# Filters.net
KiCad netlist of a schematic drawn in Altium Designer
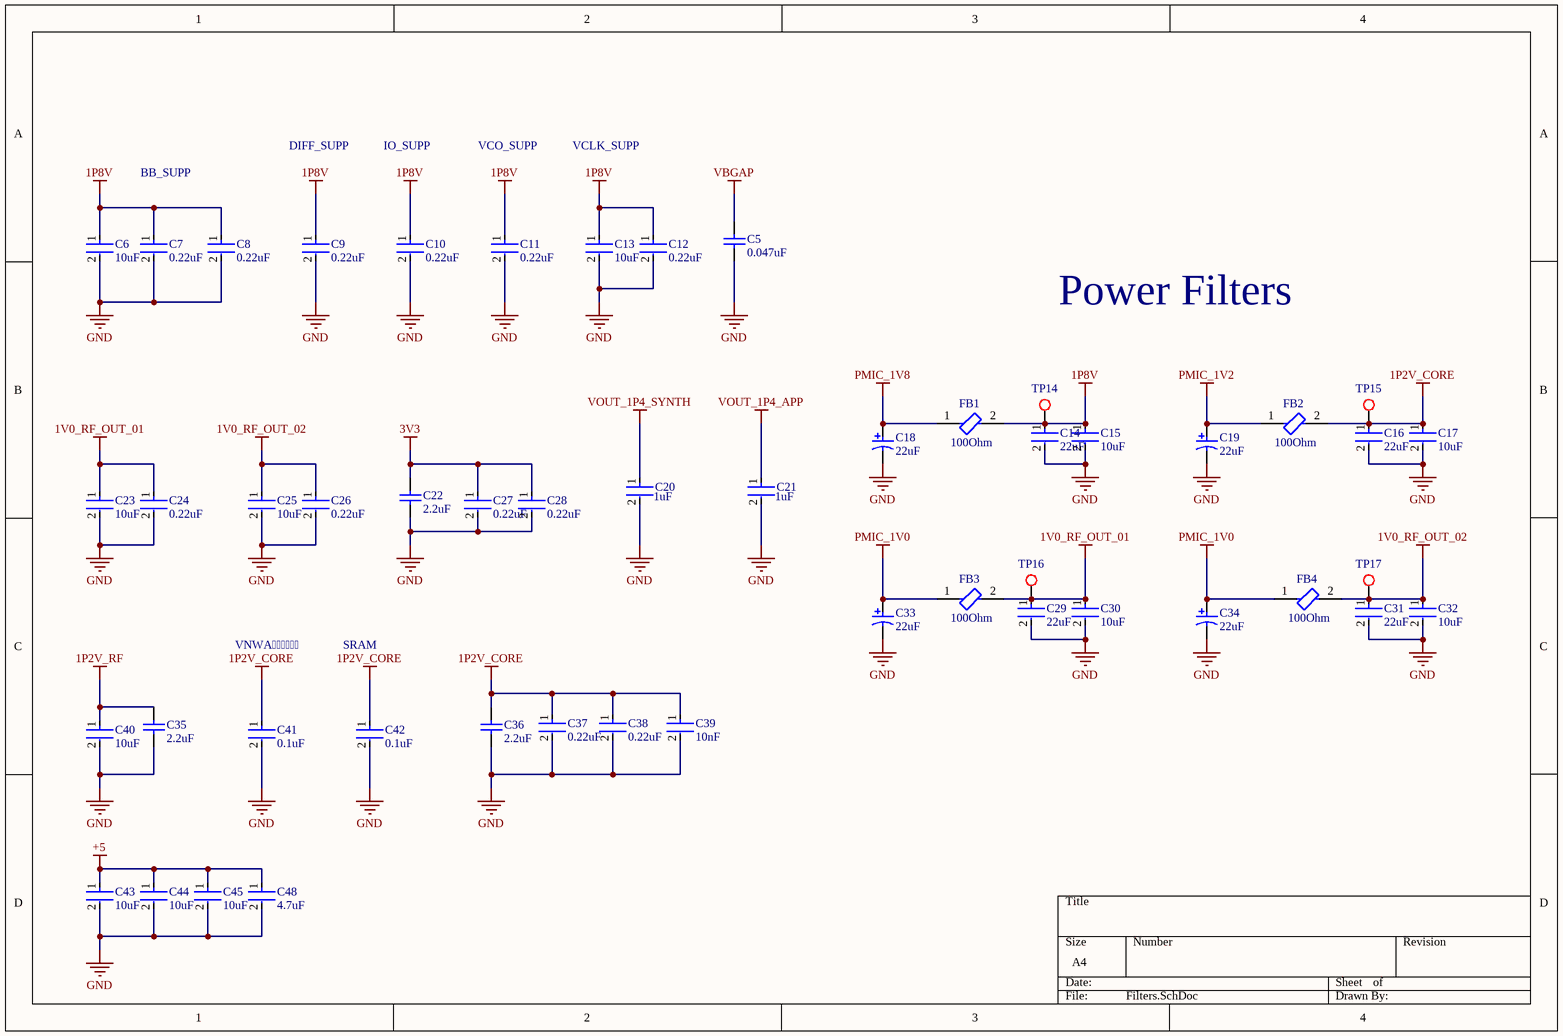
[diagram p0: Filters.SchDoc]

(export (version "E")
  (design (tool "Eeschema 10.0.6"))
  (components
    (comp (ref "C5")
      (value "0.047uF")
      (footprint "CAPC1608X90X35NL15T15")
      (fields
        (field (name "MANUFACTURER") "AVX Interconnect / Elco")
        (field (name "PART NUMBER") "06035F473K4T2A")
      )
      (libsource (lib "Altium Content Vault") (part "CAP"))
    )
    (comp (ref "C6")
      (value "10uF")
      (footprint "FP-GRM18-0_15-MFG")
      (description "CAP CER 10UF 10V X5R 0603")
      (fields
        (field (name "OCTOPART") "https://octopart.com/grm188r61a106ke69d-murata-22851381")
        (field (name "MANUFACTURER PART NUMBER") "GRM188R61A106KE69D")
      )
      (libsource (lib "Altium Content Vault") (part "11868f565c42a9108669ba33697ecf6"))
    )
    (comp (ref "C7")
      (value "0.22uF")
      (footprint "FP-C0603C-CF-MFG")
      (description "C0603 0.22 μF X7R 30ppm/°C 10.00% 10 V")
      (fields (field (name "TOLERANCE") "0.1") (field (name "MANUFACTURER PART NUMBER") "C0603C224K8RAC"))
      (libsource (lib "Altium Content Vault") (part "b4654b650e69147ec39a6b967a45e02"))
    )
    (comp (ref "C8")
      (value "0.22uF")
      (footprint "FP-C0603C-CF-MFG")
      (description "C0603 0.22 μF X7R 30ppm/°C 10.00% 10 V")
      (fields (field (name "TOLERANCE") "0.1") (field (name "MANUFACTURER PART NUMBER") "C0603C224K8RAC"))
      (libsource (lib "Altium Content Vault") (part "b4654b650e69147ec39a6b967a45e02"))
    )
    (comp (ref "C9")
      (value "0.22uF")
      (footprint "FP-C0603C-CF-MFG")
      (description "C0603 0.22 μF X7R 30ppm/°C 10.00% 10 V")
      (fields (field (name "TOLERANCE") "0.1") (field (name "MANUFACTURER PART NUMBER") "C0603C224K8RAC"))
      (libsource (lib "Altium Content Vault") (part "b4654b650e69147ec39a6b967a45e02"))
    )
    (comp (ref "C10")
      (value "0.22uF")
      (footprint "FP-C0603C-CF-MFG")
      (description "C0603 0.22 μF X7R 30ppm/°C 10.00% 10 V")
      (fields (field (name "TOLERANCE") "0.1") (field (name "MANUFACTURER PART NUMBER") "C0603C224K8RAC"))
      (libsource (lib "Altium Content Vault") (part "b4654b650e69147ec39a6b967a45e02"))
    )
    (comp (ref "C11")
      (value "0.22uF")
      (footprint "FP-C0603C-CF-MFG")
      (description "C0603 0.22 μF X7R 30ppm/°C 10.00% 10 V")
      (fields (field (name "TOLERANCE") "0.1") (field (name "MANUFACTURER PART NUMBER") "C0603C224K8RAC"))
      (libsource (lib "Altium Content Vault") (part "b4654b650e69147ec39a6b967a45e02"))
    )
    (comp (ref "C12")
      (value "0.22uF")
      (footprint "FP-C0603C-CF-MFG")
      (description "C0603 0.22 μF X7R 30ppm/°C 10.00% 10 V")
      (fields (field (name "TOLERANCE") "0.1") (field (name "MANUFACTURER PART NUMBER") "C0603C224K8RAC"))
      (libsource (lib "Altium Content Vault") (part "b4654b650e69147ec39a6b967a45e02"))
    )
    (comp (ref "C13")
      (value "10uF")
      (footprint "FP-GRM18-0_15-MFG")
      (description "CAP CER 10UF 10V X5R 0603")
      (fields
        (field (name "OCTOPART") "https://octopart.com/grm188r61a106ke69d-murata-22851381")
        (field (name "MANUFACTURER PART NUMBER") "GRM188R61A106KE69D")
      )
      (libsource (lib "Altium Content Vault") (part "11868f565c42a9108669ba33697ecf6"))
    )
    (comp (ref "C14")
      (value "22uF")
      (footprint "FP-CL21-IPC_C")
      (description "CL21 Series 0805 22uF 4V ±20% Tolerance X6S Multilayer Ceramic Chip Capacitor")
      (fields (field (name "TOLERANCE") "20%"))
      (libsource (lib "Altium Content Vault") (part "b4654b650e69147ec39a6b967a45e02"))
    )
    (comp (ref "C15")
      (value "10uF")
      (footprint "FP-GRM18-0_15-MFG")
      (description "CAP CER 10UF 10V X5R 0603")
      (fields
        (field (name "OCTOPART") "https://octopart.com/grm188r61a106ke69d-murata-22851381")
        (field (name "MANUFACTURER PART NUMBER") "GRM188R61A106KE69D")
      )
      (libsource (lib "Altium Content Vault") (part "11868f565c42a9108669ba33697ecf6"))
    )
    (comp (ref "C16")
      (value "22uF")
      (footprint "FP-CL21-IPC_C")
      (description "CL21 Series 0805 22uF 4V ±20% Tolerance X6S Multilayer Ceramic Chip Capacitor")
      (fields (field (name "TOLERANCE") "20%"))
      (libsource (lib "Altium Content Vault") (part "b4654b650e69147ec39a6b967a45e02"))
    )
    (comp (ref "C17")
      (value "10uF")
      (footprint "FP-GRM18-0_15-MFG")
      (description "CAP CER 10UF 10V X5R 0603")
      (fields
        (field (name "OCTOPART") "https://octopart.com/grm188r61a106ke69d-murata-22851381")
        (field (name "MANUFACTURER PART NUMBER") "GRM188R61A106KE69D")
      )
      (libsource (lib "Altium Content Vault") (part "11868f565c42a9108669ba33697ecf6"))
    )
    (comp (ref "C18")
      (value "22uF")
      (footprint "NIC-CAPA2-4X5.8_V")
      (fields (field (name "MANUFACTURER") "Nichicon") (field (name "PARTNUMBER") "UUD1A220MCL1GS"))
      (libsource (lib "Altium Content Vault") (part "NIC-CAP-P-2"))
    )
    (comp (ref "C19")
      (value "22uF")
      (footprint "NIC-CAPA2-4X5.8_V")
      (fields (field (name "MANUFACTURER") "Nichicon") (field (name "PARTNUMBER") "UUD1A220MCL1GS"))
      (libsource (lib "Altium Content Vault") (part "NIC-CAP-P-2"))
    )
    (comp (ref "C20")
      (value "1uF")
      (footprint "FP-CL10-IPC_C")
      (description "Cap Ceramic 1uF 10V X5R ±10% Pad SMD 0603 +85°C T/R")
      (fields (field (name "VOLTAGE") "10V") (field (name "TOLERANCE") "10%"))
      (libsource (lib "Altium Content Vault") (part "b4654b650e69147ec39a6b967a45e02"))
    )
    (comp (ref "C21")
      (value "1uF")
      (footprint "FP-CL10-IPC_C")
      (description "Cap Ceramic 1uF 10V X5R ±10% Pad SMD 0603 +85°C T/R")
      (fields (field (name "VOLTAGE") "10V") (field (name "TOLERANCE") "10%"))
      (libsource (lib "Altium Content Vault") (part "b4654b650e69147ec39a6b967a45e02"))
    )
    (comp (ref "C22")
      (value "2.2uF")
      (footprint "CAPC0603(1608)100_N")
      (description "CAP 2.2uF 16V -20% to +80% 0603 (1608 Metric) Thickness 1mm SMD")
      (fields (field (name "TOLERANCE") "-20% to +80%"))
      (libsource (lib "Altium Content Vault") (part "CAP"))
    )
    (comp (ref "C23")
      (value "10uF")
      (footprint "FP-GRM18-0_15-MFG")
      (description "CAP CER 10UF 10V X5R 0603")
      (fields
        (field (name "OCTOPART") "https://octopart.com/grm188r61a106ke69d-murata-22851381")
        (field (name "MANUFACTURER PART NUMBER") "GRM188R61A106KE69D")
      )
      (libsource (lib "Altium Content Vault") (part "11868f565c42a9108669ba33697ecf6"))
    )
    (comp (ref "C24")
      (value "0.22uF")
      (footprint "FP-C0603C-CF-MFG")
      (description "C0603 0.22 μF X7R 30ppm/°C 10.00% 10 V")
      (fields (field (name "TOLERANCE") "0.1") (field (name "MANUFACTURER PART NUMBER") "C0603C224K8RAC"))
      (libsource (lib "Altium Content Vault") (part "b4654b650e69147ec39a6b967a45e02"))
    )
    (comp (ref "C25")
      (value "10uF")
      (footprint "FP-GRM18-0_15-MFG")
      (description "CAP CER 10UF 10V X5R 0603")
      (fields
        (field (name "OCTOPART") "https://octopart.com/grm188r61a106ke69d-murata-22851381")
        (field (name "MANUFACTURER PART NUMBER") "GRM188R61A106KE69D")
      )
      (libsource (lib "Altium Content Vault") (part "11868f565c42a9108669ba33697ecf6"))
    )
    (comp (ref "C26")
      (value "0.22uF")
      (footprint "FP-C0603C-CF-MFG")
      (description "C0603 0.22 μF X7R 30ppm/°C 10.00% 10 V")
      (fields (field (name "TOLERANCE") "0.1") (field (name "MANUFACTURER PART NUMBER") "C0603C224K8RAC"))
      (libsource (lib "Altium Content Vault") (part "b4654b650e69147ec39a6b967a45e02"))
    )
    (comp (ref "C27")
      (value "0.22uF")
      (footprint "FP-C0603C-CF-MFG")
      (description "C0603 0.22 μF X7R 30ppm/°C 10.00% 10 V")
      (fields (field (name "TOLERANCE") "0.1") (field (name "MANUFACTURER PART NUMBER") "C0603C224K8RAC"))
      (libsource (lib "Altium Content Vault") (part "b4654b650e69147ec39a6b967a45e02"))
    )
    (comp (ref "C28")
      (value "0.22uF")
      (footprint "FP-C0603C-CF-MFG")
      (description "C0603 0.22 μF X7R 30ppm/°C 10.00% 10 V")
      (fields (field (name "TOLERANCE") "0.1") (field (name "MANUFACTURER PART NUMBER") "C0603C224K8RAC"))
      (libsource (lib "Altium Content Vault") (part "b4654b650e69147ec39a6b967a45e02"))
    )
    (comp (ref "C29")
      (value "22uF")
      (footprint "FP-CL21-IPC_C")
      (description "CL21 Series 0805 22uF 4V ±20% Tolerance X6S Multilayer Ceramic Chip Capacitor")
      (fields (field (name "TOLERANCE") "20%"))
      (libsource (lib "Altium Content Vault") (part "b4654b650e69147ec39a6b967a45e02"))
    )
    (comp (ref "C30")
      (value "10uF")
      (footprint "FP-GRM18-0_15-MFG")
      (description "CAP CER 10UF 10V X5R 0603")
      (fields
        (field (name "OCTOPART") "https://octopart.com/grm188r61a106ke69d-murata-22851381")
        (field (name "MANUFACTURER PART NUMBER") "GRM188R61A106KE69D")
      )
      (libsource (lib "Altium Content Vault") (part "11868f565c42a9108669ba33697ecf6"))
    )
    (comp (ref "C31")
      (value "22uF")
      (footprint "FP-CL21-IPC_C")
      (description "CL21 Series 0805 22uF 4V ±20% Tolerance X6S Multilayer Ceramic Chip Capacitor")
      (fields (field (name "TOLERANCE") "20%"))
      (libsource (lib "Altium Content Vault") (part "b4654b650e69147ec39a6b967a45e02"))
    )
    (comp (ref "C32")
      (value "10uF")
      (footprint "FP-GRM18-0_15-MFG")
      (description "CAP CER 10UF 10V X5R 0603")
      (fields
        (field (name "OCTOPART") "https://octopart.com/grm188r61a106ke69d-murata-22851381")
        (field (name "MANUFACTURER PART NUMBER") "GRM188R61A106KE69D")
      )
      (libsource (lib "Altium Content Vault") (part "11868f565c42a9108669ba33697ecf6"))
    )
    (comp (ref "C33")
      (value "22uF")
      (footprint "NIC-CAPA2-4X5.8_V")
      (fields (field (name "MANUFACTURER") "Nichicon") (field (name "PARTNUMBER") "UUD1A220MCL1GS"))
      (libsource (lib "Altium Content Vault") (part "NIC-CAP-P-2"))
    )
    (comp (ref "C34")
      (value "22uF")
      (footprint "NIC-CAPA2-4X5.8_V")
      (fields (field (name "MANUFACTURER") "Nichicon") (field (name "PARTNUMBER") "UUD1A220MCL1GS"))
      (libsource (lib "Altium Content Vault") (part "NIC-CAP-P-2"))
    )
    (comp (ref "C35")
      (value "2.2uF")
      (footprint "CAPC0603(1608)100_N")
      (description "CAP 2.2uF 16V -20% to +80% 0603 (1608 Metric) Thickness 1mm SMD")
      (fields (field (name "TOLERANCE") "-20% to +80%"))
      (libsource (lib "Altium Content Vault") (part "CAP"))
    )
    (comp (ref "C36")
      (value "2.2uF")
      (footprint "CAPC0603(1608)100_N")
      (description "CAP 2.2uF 16V -20% to +80% 0603 (1608 Metric) Thickness 1mm SMD")
      (fields (field (name "TOLERANCE") "-20% to +80%"))
      (libsource (lib "Altium Content Vault") (part "CAP"))
    )
    (comp (ref "C37")
      (value "0.22uF")
      (footprint "FP-C0603C-CF-MFG")
      (description "C0603 0.22 μF X7R 30ppm/°C 10.00% 10 V")
      (fields (field (name "TOLERANCE") "0.1") (field (name "MANUFACTURER PART NUMBER") "C0603C224K8RAC"))
      (libsource (lib "Altium Content Vault") (part "b4654b650e69147ec39a6b967a45e02"))
    )
    (comp (ref "C38")
      (value "0.22uF")
      (footprint "FP-C0603C-CF-MFG")
      (description "C0603 0.22 μF X7R 30ppm/°C 10.00% 10 V")
      (fields (field (name "TOLERANCE") "0.1") (field (name "MANUFACTURER PART NUMBER") "C0603C224K8RAC"))
      (libsource (lib "Altium Content Vault") (part "b4654b650e69147ec39a6b967a45e02"))
    )
    (comp (ref "C39")
      (value "10nF")
      (footprint "FP-CGA3E-0_3-0_1-IPC_A")
      (description "Cap Ceramic 10nF 100V X8R 10% Pad SMD 0603 +150°C Automotive T/R")
      (fields (field (name "TOLERANCE") "10%"))
      (libsource (lib "Altium Content Vault") (part "b4654b650e69147ec39a6b967a45e02"))
    )
    (comp (ref "C40")
      (value "10uF")
      (footprint "FP-GRM18-0_15-MFG")
      (description "CAP CER 10UF 10V X5R 0603")
      (fields
        (field (name "OCTOPART") "https://octopart.com/grm188r61a106ke69d-murata-22851381")
        (field (name "MANUFACTURER PART NUMBER") "GRM188R61A106KE69D")
      )
      (libsource (lib "Altium Content Vault") (part "11868f565c42a9108669ba33697ecf6"))
    )
    (comp (ref "C41")
      (value "0.1uF")
      (footprint "FP-CC0603-DA-MFG")
      (description "CAP CER 0.1UF 10V X7R 0603")
      (fields
        (field (name "OCTOPART") "https://octopart.com/cc0603krx7r6bb104-yageo-9291607")
        (field (name "TOLERANCE") "0.1")
      )
      (libsource (lib "Altium Content Vault") (part "11868f565c42a9108669ba33697ecf6"))
    )
    (comp (ref "C42")
      (value "0.1uF")
      (footprint "FP-CC0603-DA-MFG")
      (description "CAP CER 0.1UF 10V X7R 0603")
      (fields
        (field (name "OCTOPART") "https://octopart.com/cc0603krx7r6bb104-yageo-9291607")
        (field (name "TOLERANCE") "0.1")
      )
      (libsource (lib "Altium Content Vault") (part "11868f565c42a9108669ba33697ecf6"))
    )
    (comp (ref "C43")
      (value "10uF")
      (footprint "FP-GRM18-0_15-MFG")
      (description "CAP CER 10UF 10V X5R 0603")
      (fields
        (field (name "OCTOPART") "https://octopart.com/grm188r61a106ke69d-murata-22851381")
        (field (name "MANUFACTURER PART NUMBER") "GRM188R61A106KE69D")
      )
      (libsource (lib "Altium Content Vault") (part "11868f565c42a9108669ba33697ecf6"))
    )
    (comp (ref "C44")
      (value "10uF")
      (footprint "FP-GRM18-0_15-MFG")
      (description "CAP CER 10UF 10V X5R 0603")
      (fields
        (field (name "OCTOPART") "https://octopart.com/grm188r61a106ke69d-murata-22851381")
        (field (name "MANUFACTURER PART NUMBER") "GRM188R61A106KE69D")
      )
      (libsource (lib "Altium Content Vault") (part "11868f565c42a9108669ba33697ecf6"))
    )
    (comp (ref "C45")
      (value "10uF")
      (footprint "FP-GRM18-0_15-MFG")
      (description "CAP CER 10UF 10V X5R 0603")
      (fields
        (field (name "OCTOPART") "https://octopart.com/grm188r61a106ke69d-murata-22851381")
        (field (name "MANUFACTURER PART NUMBER") "GRM188R61A106KE69D")
      )
      (libsource (lib "Altium Content Vault") (part "11868f565c42a9108669ba33697ecf6"))
    )
    (comp (ref "C48")
      (value "4.7uF")
      (footprint "FP-CL10-IPC_A")
      (description "Cap Ceramic 4.7uF 6.3V X6S ±10% Pad SMD 0603 +105°C T/R")
      (fields (field (name "TOLERANCE") "10%"))
      (libsource (lib "Altium Content Vault") (part "b4654b650e69147ec39a6b967a45e02"))
    )
    (comp (ref "FB1")
      (value "100Ohm")
      (footprint "FP-MPZ1608-0_8-MFG")
      (description "Power line Ferrite Bead 100Ω @ 100MHz 2A DCR 0.04Ω AEC-Q200 SMD 0603")
      (fields (field (name "TOLERANCE") "25%"))
      (libsource (lib "Altium Content Vault") (part "5f30dd21d616792df468990f7003faa"))
    )
    (comp (ref "FB2")
      (value "100Ohm")
      (footprint "FP-MPZ1608-0_8-MFG")
      (description "Power line Ferrite Bead 100Ω @ 100MHz 2A DCR 0.04Ω AEC-Q200 SMD 0603")
      (fields (field (name "TOLERANCE") "25%"))
      (libsource (lib "Altium Content Vault") (part "5f30dd21d616792df468990f7003faa"))
    )
    (comp (ref "FB3")
      (value "100Ohm")
      (footprint "FP-MPZ1608-0_8-MFG")
      (description "Power line Ferrite Bead 100Ω @ 100MHz 2A DCR 0.04Ω AEC-Q200 SMD 0603")
      (fields (field (name "TOLERANCE") "25%"))
      (libsource (lib "Altium Content Vault") (part "5f30dd21d616792df468990f7003faa"))
    )
    (comp (ref "FB4")
      (value "100Ohm")
      (footprint "FP-MPZ1608-0_8-MFG")
      (description "Power line Ferrite Bead 100Ω @ 100MHz 2A DCR 0.04Ω AEC-Q200 SMD 0603")
      (fields (field (name "TOLERANCE") "25%"))
      (libsource (lib "Altium Content Vault") (part "5f30dd21d616792df468990f7003faa"))
    )
    (comp (ref "TP14") (value "TP_1") (footprint "Testpoint") (libsource (lib "Schlib1") (part "Testpoint")))
    (comp (ref "TP15") (value "TP_1") (footprint "Testpoint") (libsource (lib "Schlib1") (part "Testpoint")))
    (comp (ref "TP16") (value "TP_1") (footprint "Testpoint") (libsource (lib "Schlib1") (part "Testpoint")))
    (comp (ref "TP17") (value "TP_1") (footprint "Testpoint") (libsource (lib "Schlib1") (part "Testpoint")))
  )
  (nets
    (net (code "1") (name "+5") (class "Default")
      (node (ref "C43") (pin "1") (pinfunction "1_1") (pintype "passive"))
      (node (ref "C44") (pin "1") (pinfunction "1_1") (pintype "passive"))
      (node (ref "C45") (pin "1") (pinfunction "1_1") (pintype "passive"))
      (node (ref "C48") (pin "1") (pinfunction "1_1") (pintype "passive"))
    )
    (net (code "2") (name "1P2V_CORE") (class "Default")
      (node (ref "C16") (pin "1") (pinfunction "1_1") (pintype "passive"))
      (node (ref "C17") (pin "1") (pinfunction "1_1") (pintype "passive"))
      (node (ref "C36") (pin "2") (pinfunction "2_2") (pintype "passive"))
      (node (ref "C37") (pin "1") (pinfunction "1_1") (pintype "passive"))
      (node (ref "C38") (pin "1") (pinfunction "1_1") (pintype "passive"))
      (node (ref "C39") (pin "1") (pinfunction "1_1") (pintype "passive"))
      (node (ref "C41") (pin "1") (pinfunction "1_1") (pintype "passive"))
      (node (ref "C42") (pin "1") (pinfunction "1_1") (pintype "passive"))
      (node (ref "FB2") (pin "2") (pinfunction "2_2") (pintype "passive"))
      (node (ref "TP15") (pin "0") (pinfunction "0_0") (pintype "passive"))
    )
    (net (code "3") (name "1P2V_RF") (class "Default")
      (node (ref "C35") (pin "2") (pinfunction "2_2") (pintype "passive"))
      (node (ref "C40") (pin "1") (pinfunction "1_1") (pintype "passive"))
    )
    (net (code "4") (name "1P8V") (class "Default")
      (node (ref "C10") (pin "1") (pinfunction "1_1") (pintype "passive"))
      (node (ref "C11") (pin "1") (pinfunction "1_1") (pintype "passive"))
      (node (ref "C12") (pin "1") (pinfunction "1_1") (pintype "passive"))
      (node (ref "C13") (pin "1") (pinfunction "1_1") (pintype "passive"))
      (node (ref "C14") (pin "1") (pinfunction "1_1") (pintype "passive"))
      (node (ref "C15") (pin "1") (pinfunction "1_1") (pintype "passive"))
      (node (ref "C6") (pin "1") (pinfunction "1_1") (pintype "passive"))
      (node (ref "C7") (pin "1") (pinfunction "1_1") (pintype "passive"))
      (node (ref "C8") (pin "1") (pinfunction "1_1") (pintype "passive"))
      (node (ref "C9") (pin "1") (pinfunction "1_1") (pintype "passive"))
      (node (ref "FB1") (pin "2") (pinfunction "2_2") (pintype "passive"))
      (node (ref "TP14") (pin "0") (pinfunction "0_0") (pintype "passive"))
    )
    (net (code "5") (name "1V0_RF_OUT_01") (class "Default")
      (node (ref "C23") (pin "1") (pinfunction "1_1") (pintype "passive"))
      (node (ref "C24") (pin "1") (pinfunction "1_1") (pintype "passive"))
      (node (ref "C29") (pin "1") (pinfunction "1_1") (pintype "passive"))
      (node (ref "C30") (pin "1") (pinfunction "1_1") (pintype "passive"))
      (node (ref "FB3") (pin "2") (pinfunction "2_2") (pintype "passive"))
      (node (ref "TP16") (pin "0") (pinfunction "0_0") (pintype "passive"))
    )
    (net (code "6") (name "1V0_RF_OUT_02") (class "Default")
      (node (ref "C25") (pin "1") (pinfunction "1_1") (pintype "passive"))
      (node (ref "C26") (pin "1") (pinfunction "1_1") (pintype "passive"))
      (node (ref "C31") (pin "1") (pinfunction "1_1") (pintype "passive"))
      (node (ref "C32") (pin "1") (pinfunction "1_1") (pintype "passive"))
      (node (ref "FB4") (pin "2") (pinfunction "2_2") (pintype "passive"))
      (node (ref "TP17") (pin "0") (pinfunction "0_0") (pintype "passive"))
    )
    (net (code "7") (name "3V3") (class "Default")
      (node (ref "C22") (pin "2") (pinfunction "2_2") (pintype "passive"))
      (node (ref "C27") (pin "1") (pinfunction "1_1") (pintype "passive"))
      (node (ref "C28") (pin "1") (pinfunction "1_1") (pintype "passive"))
    )
    (net (code "8") (name "GND") (class "Default")
      (node (ref "C10") (pin "2") (pinfunction "2_2") (pintype "passive"))
      (node (ref "C11") (pin "2") (pinfunction "2_2") (pintype "passive"))
      (node (ref "C12") (pin "2") (pinfunction "2_2") (pintype "passive"))
      (node (ref "C13") (pin "2") (pinfunction "2_2") (pintype "passive"))
      (node (ref "C14") (pin "2") (pinfunction "2_2") (pintype "passive"))
      (node (ref "C15") (pin "2") (pinfunction "2_2") (pintype "passive"))
      (node (ref "C16") (pin "2") (pinfunction "2_2") (pintype "passive"))
      (node (ref "C17") (pin "2") (pinfunction "2_2") (pintype "passive"))
      (node (ref "C18") (pin "2") (pinfunction "2_2") (pintype "passive"))
      (node (ref "C19") (pin "2") (pinfunction "2_2") (pintype "passive"))
      (node (ref "C20") (pin "2") (pinfunction "2_2") (pintype "passive"))
      (node (ref "C21") (pin "2") (pinfunction "2_2") (pintype "passive"))
      (node (ref "C22") (pin "1") (pinfunction "1_1") (pintype "passive"))
      (node (ref "C23") (pin "2") (pinfunction "2_2") (pintype "passive"))
      (node (ref "C24") (pin "2") (pinfunction "2_2") (pintype "passive"))
      (node (ref "C25") (pin "2") (pinfunction "2_2") (pintype "passive"))
      (node (ref "C26") (pin "2") (pinfunction "2_2") (pintype "passive"))
      (node (ref "C27") (pin "2") (pinfunction "2_2") (pintype "passive"))
      (node (ref "C28") (pin "2") (pinfunction "2_2") (pintype "passive"))
      (node (ref "C29") (pin "2") (pinfunction "2_2") (pintype "passive"))
      (node (ref "C30") (pin "2") (pinfunction "2_2") (pintype "passive"))
      (node (ref "C31") (pin "2") (pinfunction "2_2") (pintype "passive"))
      (node (ref "C32") (pin "2") (pinfunction "2_2") (pintype "passive"))
      (node (ref "C33") (pin "2") (pinfunction "2_2") (pintype "passive"))
      (node (ref "C34") (pin "2") (pinfunction "2_2") (pintype "passive"))
      (node (ref "C35") (pin "1") (pinfunction "1_1") (pintype "passive"))
      (node (ref "C36") (pin "1") (pinfunction "1_1") (pintype "passive"))
      (node (ref "C37") (pin "2") (pinfunction "2_2") (pintype "passive"))
      (node (ref "C38") (pin "2") (pinfunction "2_2") (pintype "passive"))
      (node (ref "C39") (pin "2") (pinfunction "2_2") (pintype "passive"))
      (node (ref "C40") (pin "2") (pinfunction "2_2") (pintype "passive"))
      (node (ref "C41") (pin "2") (pinfunction "2_2") (pintype "passive"))
      (node (ref "C42") (pin "2") (pinfunction "2_2") (pintype "passive"))
      (node (ref "C43") (pin "2") (pinfunction "2_2") (pintype "passive"))
      (node (ref "C44") (pin "2") (pinfunction "2_2") (pintype "passive"))
      (node (ref "C45") (pin "2") (pinfunction "2_2") (pintype "passive"))
      (node (ref "C48") (pin "2") (pinfunction "2_2") (pintype "passive"))
      (node (ref "C5") (pin "1") (pinfunction "1_1") (pintype "passive"))
      (node (ref "C6") (pin "2") (pinfunction "2_2") (pintype "passive"))
      (node (ref "C7") (pin "2") (pinfunction "2_2") (pintype "passive"))
      (node (ref "C8") (pin "2") (pinfunction "2_2") (pintype "passive"))
      (node (ref "C9") (pin "2") (pinfunction "2_2") (pintype "passive"))
    )
    (net (code "9") (name "PMIC_1V0") (class "Default")
      (node (ref "C33") (pin "1") (pinfunction "1_1") (pintype "passive"))
      (node (ref "C34") (pin "1") (pinfunction "1_1") (pintype "passive"))
      (node (ref "FB3") (pin "1") (pinfunction "1_1") (pintype "passive"))
      (node (ref "FB4") (pin "1") (pinfunction "1_1") (pintype "passive"))
    )
    (net (code "10") (name "PMIC_1V2") (class "Default")
      (node (ref "C19") (pin "1") (pinfunction "1_1") (pintype "passive"))
      (node (ref "FB2") (pin "1") (pinfunction "1_1") (pintype "passive"))
    )
    (net (code "11") (name "PMIC_1V8") (class "Default")
      (node (ref "C18") (pin "1") (pinfunction "1_1") (pintype "passive"))
      (node (ref "FB1") (pin "1") (pinfunction "1_1") (pintype "passive"))
    )
    (net (code "12") (name "VBGAP") (class "Default")
      (node (ref "C5") (pin "2") (pinfunction "2_2") (pintype "passive"))
    )
    (net (code "13") (name "VOUT_1P4_APP") (class "Default")
      (node (ref "C21") (pin "1") (pinfunction "1_1") (pintype "passive"))
    )
    (net (code "14") (name "VOUT_1P4_SYNTH") (class "Default")
      (node (ref "C20") (pin "1") (pinfunction "1_1") (pintype "passive"))
    )
  )
)
